# endstop.net
KiCad netlist of a schematic drawn in Altium Designer
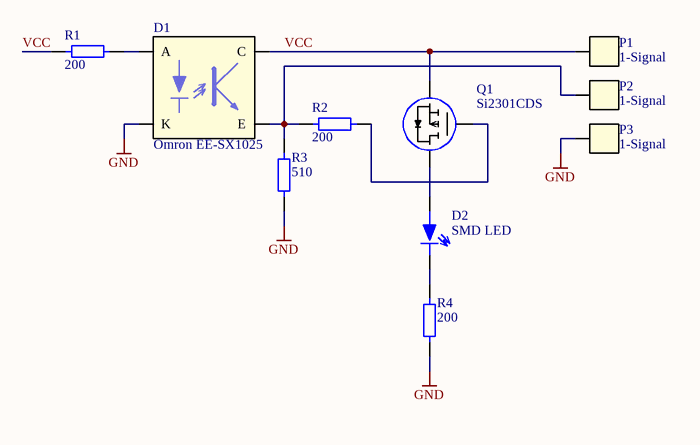
[diagram p0: endstop.SchDoc]

(export (version "E")
  (design (tool "Eeschema 10.0.6"))
  (components
    (comp (ref "D1")
      (value "Omron EE-SX1025")
      (footprint "EE-SX1025")
      (libsource (lib "AltiumDesigner") (part "EE-SX1025"))
    )
    (comp (ref "D2") (value "SMD LED") (footprint "0603") (libsource (lib "AltiumDesigner") (part "SMD LED")))
    (comp (ref "P1")
      (value "1-Signal")
      (footprint "1-SignalSmall")
      (libsource (lib "AltiumDesigner") (part "1-Signal"))
    )
    (comp (ref "P2")
      (value "1-Signal")
      (footprint "1-SignalSmall")
      (libsource (lib "AltiumDesigner") (part "1-Signal"))
    )
    (comp (ref "P3")
      (value "1-Signal")
      (footprint "1-SignalSmall")
      (libsource (lib "AltiumDesigner") (part "1-Signal"))
    )
    (comp (ref "Q1")
      (value "Si2301CDS")
      (footprint "SOT23-3")
      (libsource (lib "AltiumDesigner") (part "Si2301CDS"))
    )
    (comp (ref "R1") (value "200") (footprint "0402") (libsource (lib "AltiumDesigner") (part "Res")))
    (comp (ref "R2") (value "200") (footprint "0402") (libsource (lib "AltiumDesigner") (part "Res")))
    (comp (ref "R3") (value "510") (footprint "0402") (libsource (lib "AltiumDesigner") (part "Res")))
    (comp (ref "R4") (value "200") (footprint "0402") (libsource (lib "AltiumDesigner") (part "Res")))
  )
  (nets
    (net (code "1") (name "/VCC") (class "Default")
      (node (ref "D1") (pin "3") (pinfunction "C_3") (pintype "passive"))
      (node (ref "P1") (pin "1") (pinfunction "1_1") (pintype "passive"))
      (node (ref "Q1") (pin "2") (pinfunction "S_2") (pintype "passive"))
      (node (ref "R1") (pin "1") (pinfunction "1_1") (pintype "passive"))
    )
    (net (code "2") (name "GND") (class "Default")
      (node (ref "D1") (pin "2") (pinfunction "K_2") (pintype "passive"))
      (node (ref "P3") (pin "1") (pinfunction "1_1") (pintype "passive"))
      (node (ref "R3") (pin "1") (pinfunction "1_1") (pintype "passive"))
      (node (ref "R4") (pin "1") (pinfunction "1_1") (pintype "passive"))
    )
    (net (code "3") (name "Net-(D1-A)") (class "Default")
      (node (ref "D1") (pin "1") (pinfunction "A_1") (pintype "passive"))
      (node (ref "R1") (pin "2") (pinfunction "2_2") (pintype "passive"))
    )
    (net (code "4") (name "Net-(D1-E)") (class "Default")
      (node (ref "D1") (pin "4") (pinfunction "E_4") (pintype "passive"))
      (node (ref "P2") (pin "1") (pinfunction "1_1") (pintype "passive"))
      (node (ref "R2") (pin "1") (pinfunction "1_1") (pintype "passive"))
      (node (ref "R3") (pin "2") (pinfunction "2_2") (pintype "passive"))
    )
    (net (code "5") (name "Net-(D2-A)") (class "Default")
      (node (ref "D2") (pin "1") (pinfunction "A_1") (pintype "passive"))
      (node (ref "Q1") (pin "3") (pinfunction "D_3") (pintype "passive"))
    )
    (net (code "6") (name "Net-(D2-K)") (class "Default")
      (node (ref "D2") (pin "2") (pinfunction "K_2") (pintype "passive"))
      (node (ref "R4") (pin "2") (pinfunction "2_2") (pintype "passive"))
    )
    (net (code "7") (name "Net-(Q1-G)") (class "Default")
      (node (ref "Q1") (pin "1") (pinfunction "G_1") (pintype "passive"))
      (node (ref "R2") (pin "2") (pinfunction "2_2") (pintype "passive"))
    )
  )
)
